# PositionSensor.net
KiCad netlist of a schematic drawn in EAGLE
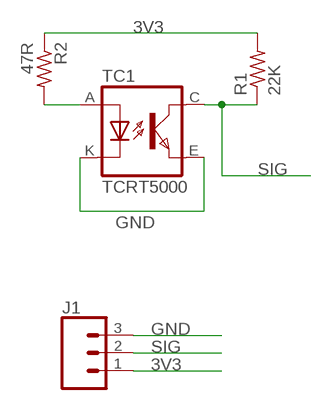
[diagram p0: schematic, sheet 1]

(export (version "E")
  (design (tool "Eeschema 10.0.6"))
  (components
    (comp (ref "J1")
      (value "CONN_03LONGPADS")
      (footprint "eagle-import:1X03_LONGPADS")
      (libsource (lib "eagle-import") (part "CONN_03LONGPADS"))
    )
    (comp (ref "R1")
      (value "22K")
      (footprint "eagle-import:0204_7")
      (libsource (lib "eagle-import") (part "R-US_0204/7"))
    )
    (comp (ref "R2")
      (value "47R")
      (footprint "eagle-import:0204_7")
      (libsource (lib "eagle-import") (part "R-US_0204/7"))
    )
    (comp (ref "TC1")
      (value "TCRT5000")
      (footprint "eagle-import:TCRT5000")
      (libsource (lib "eagle-import") (part "TCRT5000"))
    )
  )
  (nets
    (net (code "1") (name "/3V3") (class "Default")
      (node (ref "J1") (pin "1") (pinfunction "1_1") (pintype "passive"))
      (node (ref "R1") (pin "2") (pinfunction "2_2") (pintype "passive"))
      (node (ref "R2") (pin "1") (pinfunction "1_1") (pintype "passive"))
    )
    (net (code "2") (name "/GND") (class "Default")
      (node (ref "J1") (pin "3") (pinfunction "3_3") (pintype "passive"))
      (node (ref "TC1") (pin "E") (pinfunction "EMITTER_E") (pintype "passive"))
      (node (ref "TC1") (pin "K") (pinfunction "CATHODE_K") (pintype "passive"))
    )
    (net (code "3") (name "/SIG") (class "Default")
      (node (ref "J1") (pin "2") (pinfunction "2_2") (pintype "passive"))
      (node (ref "R1") (pin "1") (pinfunction "1_1") (pintype "passive"))
      (node (ref "TC1") (pin "C") (pinfunction "COLLECTOR_C") (pintype "passive"))
    )
    (net (code "4") (name "Net-(TC1-ANODE)") (class "Default")
      (node (ref "R2") (pin "2") (pinfunction "2_2") (pintype "passive"))
      (node (ref "TC1") (pin "A") (pinfunction "ANODE_A") (pintype "passive"))
    )
  )
)
